# Copy_of_EE209_Schematic.net
KiCad netlist of a schematic drawn in Altium Designer
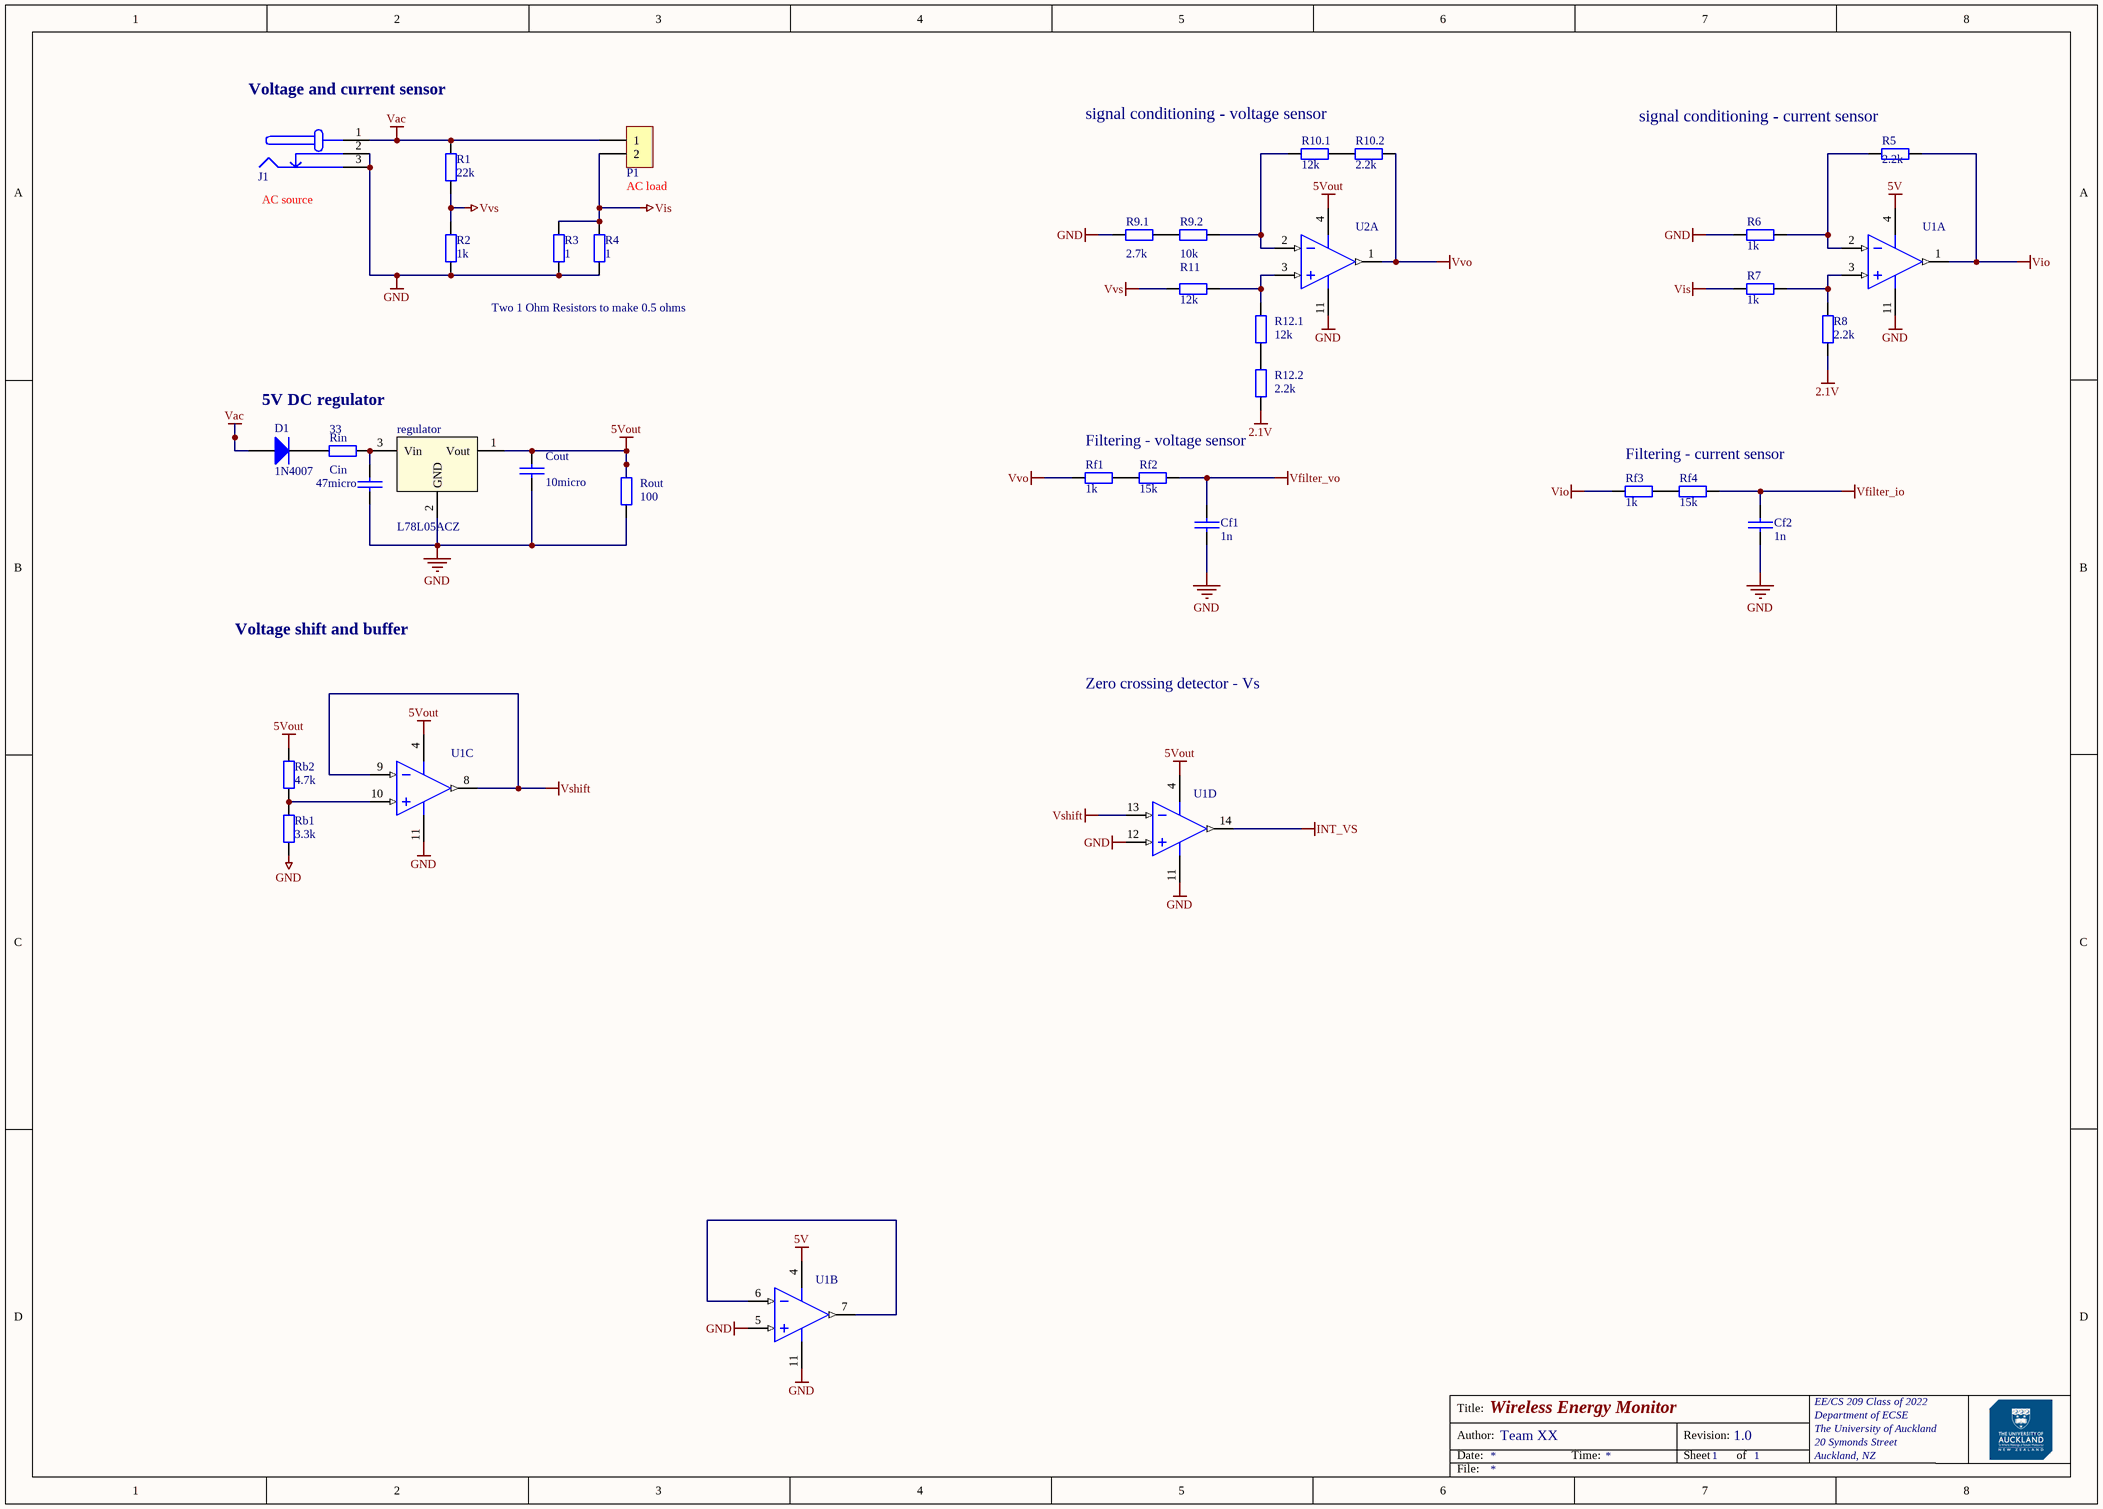
[diagram p0: Copy of EE209_Schematic.SchDoc]

(export (version "E")
  (design (tool "Eeschema 10.0.6"))
  (components
    (comp (ref "Cf1")
      (value "1n")
      (footprint "CCAP-5P0")
      (description "TH ceramic capacitor with 5mm pitch")
      (libsource (lib "EE209_Library") (part "CerCap_TH_5P0"))
    )
    (comp (ref "Cf2")
      (value "1n")
      (footprint "CCAP-5P0")
      (description "TH ceramic capacitor with 5mm pitch")
      (libsource (lib "EE209_Library") (part "CerCap_TH_5P0"))
    )
    (comp (ref "Cin")
      (value "47micro")
      (footprint "CCAP-5P0")
      (description "TH ceramic capacitor with 5mm pitch")
      (libsource (lib "EE209_Library") (part "CerCap_TH_5P0"))
    )
    (comp (ref "Cout")
      (value "10micro")
      (footprint "CCAP-5P0")
      (description "TH ceramic capacitor with 5mm pitch")
      (libsource (lib "EE209_Library") (part "CerCap_TH_5P0"))
    )
    (comp (ref "D1")
      (value "1N4007")
      (footprint "1N4007-MFG")
      (description "1N4007 1000V standard axial diode")
      (libsource (lib "EE209_Library") (part "1N4007_TH_4AX0"))
    )
    (comp (ref "J1")
      (value "DC barrel jack")
      (footprint "AC-Socket")
      (description "DC barrel jack connection to AC source")
      (libsource (lib "EE209_Library") (part "AC_Input"))
    )
    (comp (ref "P1")
      (value "Dual Banana Plugs")
      (footprint "Dual Banana Plug")
      (description "Dual banana plugs connection to the AC load")
      (fields (field (name "PUBLISHER") "Altium Limited"))
      (libsource (lib "EE209_Library") (part "AC_Output"))
    )
    (comp (ref "R1")
      (value "22k")
      (footprint "AXIAL-0.4")
      (description "Through hole resistor")
      (fields (field (name "PUBLISHER") "Altium Limited"))
      (libsource (lib "EE209_Library") (part "Res_TH_0AX4"))
    )
    (comp (ref "R2")
      (value "1k")
      (footprint "AXIAL-0.4")
      (description "Through hole resistor")
      (fields (field (name "PUBLISHER") "Altium Limited"))
      (libsource (lib "EE209_Library") (part "Res_TH_0AX4"))
    )
    (comp (ref "R3")
      (value "1")
      (footprint "AXIAL-0.4")
      (description "Through hole resistor")
      (fields (field (name "PUBLISHER") "Altium Limited"))
      (libsource (lib "EE209_Library") (part "Res_TH_0AX4"))
    )
    (comp (ref "R4")
      (value "1")
      (footprint "AXIAL-0.4")
      (description "Through hole resistor")
      (fields (field (name "PUBLISHER") "Altium Limited"))
      (libsource (lib "EE209_Library") (part "Res_TH_0AX4"))
    )
    (comp (ref "R5")
      (value "2.2k")
      (footprint "AXIAL-0.4")
      (description "Through hole resistor")
      (fields (field (name "PUBLISHER") "Altium Limited"))
      (libsource (lib "") (part "Res_TH_0AX4_1"))
    )
    (comp (ref "R6")
      (value "1k")
      (footprint "AXIAL-0.4")
      (description "Through hole resistor")
      (fields (field (name "PUBLISHER") "Altium Limited"))
      (libsource (lib "") (part "Res_TH_0AX4_1"))
    )
    (comp (ref "R7")
      (value "1k")
      (footprint "AXIAL-0.4")
      (description "Through hole resistor")
      (fields (field (name "PUBLISHER") "Altium Limited"))
      (libsource (lib "") (part "Res_TH_0AX4_1"))
    )
    (comp (ref "R8")
      (value "2.2k")
      (footprint "AXIAL-0.4")
      (description "Through hole resistor")
      (fields (field (name "PUBLISHER") "Altium Limited"))
      (libsource (lib "EE209_Library") (part "Res_TH_0AX4"))
    )
    (comp (ref "R9.1")
      (value "2.7k")
      (footprint "AXIAL-0.4")
      (description "Through hole resistor")
      (fields (field (name "PUBLISHER") "Altium Limited"))
      (libsource (lib "") (part "Res_TH_0AX4_1"))
    )
    (comp (ref "R9.2")
      (value "10k")
      (footprint "AXIAL-0.4")
      (description "Through hole resistor")
      (fields (field (name "PUBLISHER") "Altium Limited"))
      (libsource (lib "") (part "Res_TH_0AX4_1"))
    )
    (comp (ref "R10.1")
      (value "12k")
      (footprint "AXIAL-0.4")
      (description "Through hole resistor")
      (fields (field (name "PUBLISHER") "Altium Limited"))
      (libsource (lib "") (part "Res_TH_0AX4_1"))
    )
    (comp (ref "R10.2")
      (value "2.2k")
      (footprint "AXIAL-0.4")
      (description "Through hole resistor")
      (fields (field (name "PUBLISHER") "Altium Limited"))
      (libsource (lib "") (part "Res_TH_0AX4_1"))
    )
    (comp (ref "R11")
      (value "12k")
      (footprint "AXIAL-0.4")
      (description "Through hole resistor")
      (fields (field (name "PUBLISHER") "Altium Limited"))
      (libsource (lib "") (part "Res_TH_0AX4_1"))
    )
    (comp (ref "R12.1")
      (value "12k")
      (footprint "AXIAL-0.4")
      (description "Through hole resistor")
      (fields (field (name "PUBLISHER") "Altium Limited"))
      (libsource (lib "EE209_Library") (part "Res_TH_0AX4"))
    )
    (comp (ref "R12.2")
      (value "2.2k")
      (footprint "AXIAL-0.4")
      (description "Through hole resistor")
      (fields (field (name "PUBLISHER") "Altium Limited"))
      (libsource (lib "EE209_Library") (part "Res_TH_0AX4"))
    )
    (comp (ref "Rb1")
      (value "3.3k")
      (footprint "AXIAL-0.4")
      (description "Through hole resistor")
      (fields (field (name "PUBLISHER") "Altium Limited"))
      (libsource (lib "EE209_Library") (part "Res_TH_0AX4"))
    )
    (comp (ref "Rb2")
      (value "4.7k")
      (footprint "AXIAL-0.4")
      (description "Through hole resistor")
      (fields (field (name "PUBLISHER") "Altium Limited"))
      (libsource (lib "EE209_Library") (part "Res_TH_0AX4"))
    )
    (comp (ref "regulator")
      (value "L78L05ACZ")
      (footprint "TO-92")
      (description "Voltage Regulator 5V")
      (fields
        (field (name "MANUFACTURER") "ON Semiconductor")
        (field (name "MANUFACTURER PART NUMBER") "LM78L05ACZX")
      )
      (libsource (lib "EE209_Library") (part "L78L05_TH_TO92"))
    )
    (comp (ref "Rf1")
      (value "1k")
      (footprint "AXIAL-0.4")
      (description "Through hole resistor")
      (fields (field (name "PUBLISHER") "Altium Limited"))
      (libsource (lib "") (part "Res_TH_0AX4_1"))
    )
    (comp (ref "Rf2")
      (value "15k")
      (footprint "AXIAL-0.4")
      (description "Through hole resistor")
      (fields (field (name "PUBLISHER") "Altium Limited"))
      (libsource (lib "") (part "Res_TH_0AX4_1"))
    )
    (comp (ref "Rf3")
      (value "1k")
      (footprint "AXIAL-0.4")
      (description "Through hole resistor")
      (fields (field (name "PUBLISHER") "Altium Limited"))
      (libsource (lib "") (part "Res_TH_0AX4_1"))
    )
    (comp (ref "Rf4")
      (value "15k")
      (footprint "AXIAL-0.4")
      (description "Through hole resistor")
      (fields (field (name "PUBLISHER") "Altium Limited"))
      (libsource (lib "") (part "Res_TH_0AX4_1"))
    )
    (comp (ref "Rin")
      (value "33")
      (footprint "AXIAL-0.4")
      (description "Through hole resistor")
      (fields (field (name "PUBLISHER") "Altium Limited"))
      (libsource (lib "") (part "Res_TH_0AX4_1"))
    )
    (comp (ref "Rout")
      (value "100")
      (footprint "AXIAL-0.4")
      (description "Through hole resistor")
      (fields (field (name "PUBLISHER") "Altium Limited"))
      (libsource (lib "EE209_Library") (part "Res_TH_0AX4"))
    )
    (comp (ref "U1")
      (value "LM324")
      (footprint "DIP-14")
      (description "IC OPAMP GP 14DIP")
      (fields
        (field (name "MANUFACTURER") "ON Semiconductor")
        (field (name "MANUFACTURER PART NUMBER") "LM324N")
      )
      (libsource (lib "EE209_Library") (part "LM324N_TH_DIP16"))
    )
    (comp (ref "U2")
      (value "LM324")
      (footprint "DIP-14")
      (description "IC OPAMP GP 14DIP")
      (fields
        (field (name "MANUFACTURER") "ON Semiconductor")
        (field (name "MANUFACTURER PART NUMBER") "LM324N")
      )
      (libsource (lib "EE209_Library") (part "LM324N_TH_DIP16"))
    )
  )
  (nets
    (net (code "1") (name "2.1V") (class "Default")
      (node (ref "R12.2") (pin "1") (pinfunction "1_1") (pintype "passive"))
      (node (ref "R8") (pin "1") (pinfunction "1_1") (pintype "passive"))
    )
    (net (code "2") (name "5V") (class "Default")
      (node (ref "U1") (pin "4") (pinfunction "VDD_4") (pintype "power_in"))
    )
    (net (code "3") (name "5Vout") (class "Default")
      (node (ref "Cout") (pin "1") (pinfunction "1_1") (pintype "passive"))
      (node (ref "Rb2") (pin "2") (pinfunction "2_2") (pintype "passive"))
      (node (ref "Rout") (pin "2") (pinfunction "2_2") (pintype "passive"))
      (node (ref "U1") (pin "4") (pinfunction "VDD_4") (pintype "power_in"))
      (node (ref "U2") (pin "4") (pinfunction "VDD_4") (pintype "power_in"))
      (node (ref "regulator") (pin "1") (pinfunction "Vout_1") (pintype "passive"))
    )
    (net (code "4") (name "GND") (class "Default")
      (node (ref "Cf1") (pin "2") (pinfunction "2_2") (pintype "passive"))
      (node (ref "Cf2") (pin "2") (pinfunction "2_2") (pintype "passive"))
      (node (ref "Cin") (pin "2") (pinfunction "2_2") (pintype "passive"))
      (node (ref "Cout") (pin "2") (pinfunction "2_2") (pintype "passive"))
      (node (ref "J1") (pin "2") (pinfunction "GND_ALT_2") (pintype "power_in"))
      (node (ref "J1") (pin "3") (pinfunction "GND_3") (pintype "power_in"))
      (node (ref "R2") (pin "1") (pinfunction "1_1") (pintype "passive"))
      (node (ref "R3") (pin "1") (pinfunction "1_1") (pintype "passive"))
      (node (ref "R4") (pin "1") (pinfunction "1_1") (pintype "passive"))
      (node (ref "R6") (pin "1") (pinfunction "1_1") (pintype "passive"))
      (node (ref "R9.1") (pin "1") (pinfunction "1_1") (pintype "passive"))
      (node (ref "Rb1") (pin "1") (pinfunction "1_1") (pintype "passive"))
      (node (ref "Rout") (pin "1") (pinfunction "1_1") (pintype "passive"))
      (node (ref "U1") (pin "11") (pinfunction "VSS_11") (pintype "power_in"))
      (node (ref "U1") (pin "12") (pinfunction "VIND+_12") (pintype "input"))
      (node (ref "U1") (pin "5") (pinfunction "VINB+_5") (pintype "input"))
      (node (ref "U2") (pin "11") (pinfunction "VSS_11") (pintype "power_in"))
      (node (ref "regulator") (pin "2") (pinfunction "GND_2") (pintype "passive"))
    )
    (net (code "5") (name "INT_VS") (class "Default")
      (node (ref "U1") (pin "14") (pinfunction "VOUTD_14") (pintype "output"))
    )
    (net (code "6") (name "Net-(D1-K)") (class "Default")
      (node (ref "D1") (pin "2") (pinfunction "K_2") (pintype "passive"))
      (node (ref "Rin") (pin "1") (pinfunction "1_1") (pintype "passive"))
    )
    (net (code "7") (name "Net-(R9.1-Pad2)") (class "Default")
      (node (ref "R9.1") (pin "2") (pinfunction "2_2") (pintype "passive"))
      (node (ref "R9.2") (pin "1") (pinfunction "1_1") (pintype "passive"))
    )
    (net (code "8") (name "Net-(R10.1-Pad2)") (class "Default")
      (node (ref "R10.1") (pin "2") (pinfunction "2_2") (pintype "passive"))
      (node (ref "R10.2") (pin "1") (pinfunction "1_1") (pintype "passive"))
    )
    (net (code "9") (name "Net-(R12.1-Pad1)") (class "Default")
      (node (ref "R12.1") (pin "1") (pinfunction "1_1") (pintype "passive"))
      (node (ref "R12.2") (pin "2") (pinfunction "2_2") (pintype "passive"))
    )
    (net (code "10") (name "Net-(Rf1-Pad2)") (class "Default")
      (node (ref "Rf1") (pin "2") (pinfunction "2_2") (pintype "passive"))
      (node (ref "Rf2") (pin "1") (pinfunction "1_1") (pintype "passive"))
    )
    (net (code "11") (name "Net-(Rf3-Pad2)") (class "Default")
      (node (ref "Rf3") (pin "2") (pinfunction "2_2") (pintype "passive"))
      (node (ref "Rf4") (pin "1") (pinfunction "1_1") (pintype "passive"))
    )
    (net (code "12") (name "Net-(U1A-VINA+)") (class "Default")
      (node (ref "R7") (pin "2") (pinfunction "2_2") (pintype "passive"))
      (node (ref "R8") (pin "2") (pinfunction "2_2") (pintype "passive"))
      (node (ref "U1") (pin "3") (pinfunction "VINA+_3") (pintype "input"))
    )
    (net (code "13") (name "Net-(U1A-VINA-)") (class "Default")
      (node (ref "R5") (pin "1") (pinfunction "1_1") (pintype "passive"))
      (node (ref "R6") (pin "2") (pinfunction "2_2") (pintype "passive"))
      (node (ref "U1") (pin "2") (pinfunction "VINA-_2") (pintype "input"))
    )
    (net (code "14") (name "Net-(U1B-VINB-)") (class "Default")
      (node (ref "U1") (pin "6") (pinfunction "VINB-_6") (pintype "input"))
      (node (ref "U1") (pin "7") (pinfunction "VOUTB_7") (pintype "output"))
    )
    (net (code "15") (name "Net-(U1C-VINC+)") (class "Default")
      (node (ref "Rb1") (pin "2") (pinfunction "2_2") (pintype "passive"))
      (node (ref "Rb2") (pin "1") (pinfunction "1_1") (pintype "passive"))
      (node (ref "U1") (pin "10") (pinfunction "VINC+_10") (pintype "input"))
    )
    (net (code "16") (name "Net-(U2A-VINA+)") (class "Default")
      (node (ref "R11") (pin "2") (pinfunction "2_2") (pintype "passive"))
      (node (ref "R12.1") (pin "2") (pinfunction "2_2") (pintype "passive"))
      (node (ref "U2") (pin "3") (pinfunction "VINA+_3") (pintype "input"))
    )
    (net (code "17") (name "Net-(U2A-VINA-)") (class "Default")
      (node (ref "R10.1") (pin "1") (pinfunction "1_1") (pintype "passive"))
      (node (ref "R9.2") (pin "2") (pinfunction "2_2") (pintype "passive"))
      (node (ref "U2") (pin "2") (pinfunction "VINA-_2") (pintype "input"))
    )
    (net (code "18") (name "Net-(regulator-Vin)") (class "Default")
      (node (ref "Cin") (pin "1") (pinfunction "1_1") (pintype "passive"))
      (node (ref "Rin") (pin "2") (pinfunction "2_2") (pintype "passive"))
      (node (ref "regulator") (pin "3") (pinfunction "Vin_3") (pintype "passive"))
    )
    (net (code "19") (name "Vac") (class "Default")
      (node (ref "D1") (pin "1") (pinfunction "A_1") (pintype "passive"))
      (node (ref "J1") (pin "1") (pinfunction "VCC_1") (pintype "power_in"))
      (node (ref "P1") (pin "1") (pinfunction "1_1") (pintype "passive"))
      (node (ref "R1") (pin "2") (pinfunction "2_2") (pintype "passive"))
    )
    (net (code "20") (name "Vfilter_io") (class "Default")
      (node (ref "Cf2") (pin "1") (pinfunction "1_1") (pintype "passive"))
      (node (ref "Rf4") (pin "2") (pinfunction "2_2") (pintype "passive"))
    )
    (net (code "21") (name "Vfilter_vo") (class "Default")
      (node (ref "Cf1") (pin "1") (pinfunction "1_1") (pintype "passive"))
      (node (ref "Rf2") (pin "2") (pinfunction "2_2") (pintype "passive"))
    )
    (net (code "22") (name "Vio") (class "Default")
      (node (ref "R5") (pin "2") (pinfunction "2_2") (pintype "passive"))
      (node (ref "Rf3") (pin "1") (pinfunction "1_1") (pintype "passive"))
      (node (ref "U1") (pin "1") (pinfunction "VOUTA_1") (pintype "output"))
    )
    (net (code "23") (name "Vis") (class "Default")
      (node (ref "P1") (pin "2") (pinfunction "2_2") (pintype "passive"))
      (node (ref "R3") (pin "2") (pinfunction "2_2") (pintype "passive"))
      (node (ref "R4") (pin "2") (pinfunction "2_2") (pintype "passive"))
      (node (ref "R7") (pin "1") (pinfunction "1_1") (pintype "passive"))
    )
    (net (code "24") (name "Vshift") (class "Default")
      (node (ref "U1") (pin "13") (pinfunction "VIND-_13") (pintype "input"))
      (node (ref "U1") (pin "8") (pinfunction "VOUTC_8") (pintype "output"))
      (node (ref "U1") (pin "9") (pinfunction "VINC-_9") (pintype "input"))
    )
    (net (code "25") (name "Vvo") (class "Default")
      (node (ref "R10.2") (pin "2") (pinfunction "2_2") (pintype "passive"))
      (node (ref "Rf1") (pin "1") (pinfunction "1_1") (pintype "passive"))
      (node (ref "U2") (pin "1") (pinfunction "VOUTA_1") (pintype "output"))
    )
    (net (code "26") (name "Vvs") (class "Default")
      (node (ref "R1") (pin "1") (pinfunction "1_1") (pintype "passive"))
      (node (ref "R11") (pin "1") (pinfunction "1_1") (pintype "passive"))
      (node (ref "R2") (pin "2") (pinfunction "2_2") (pintype "passive"))
    )
  )
)
